# sensorNodev3.net
KiCad netlist of a schematic drawn in EAGLE
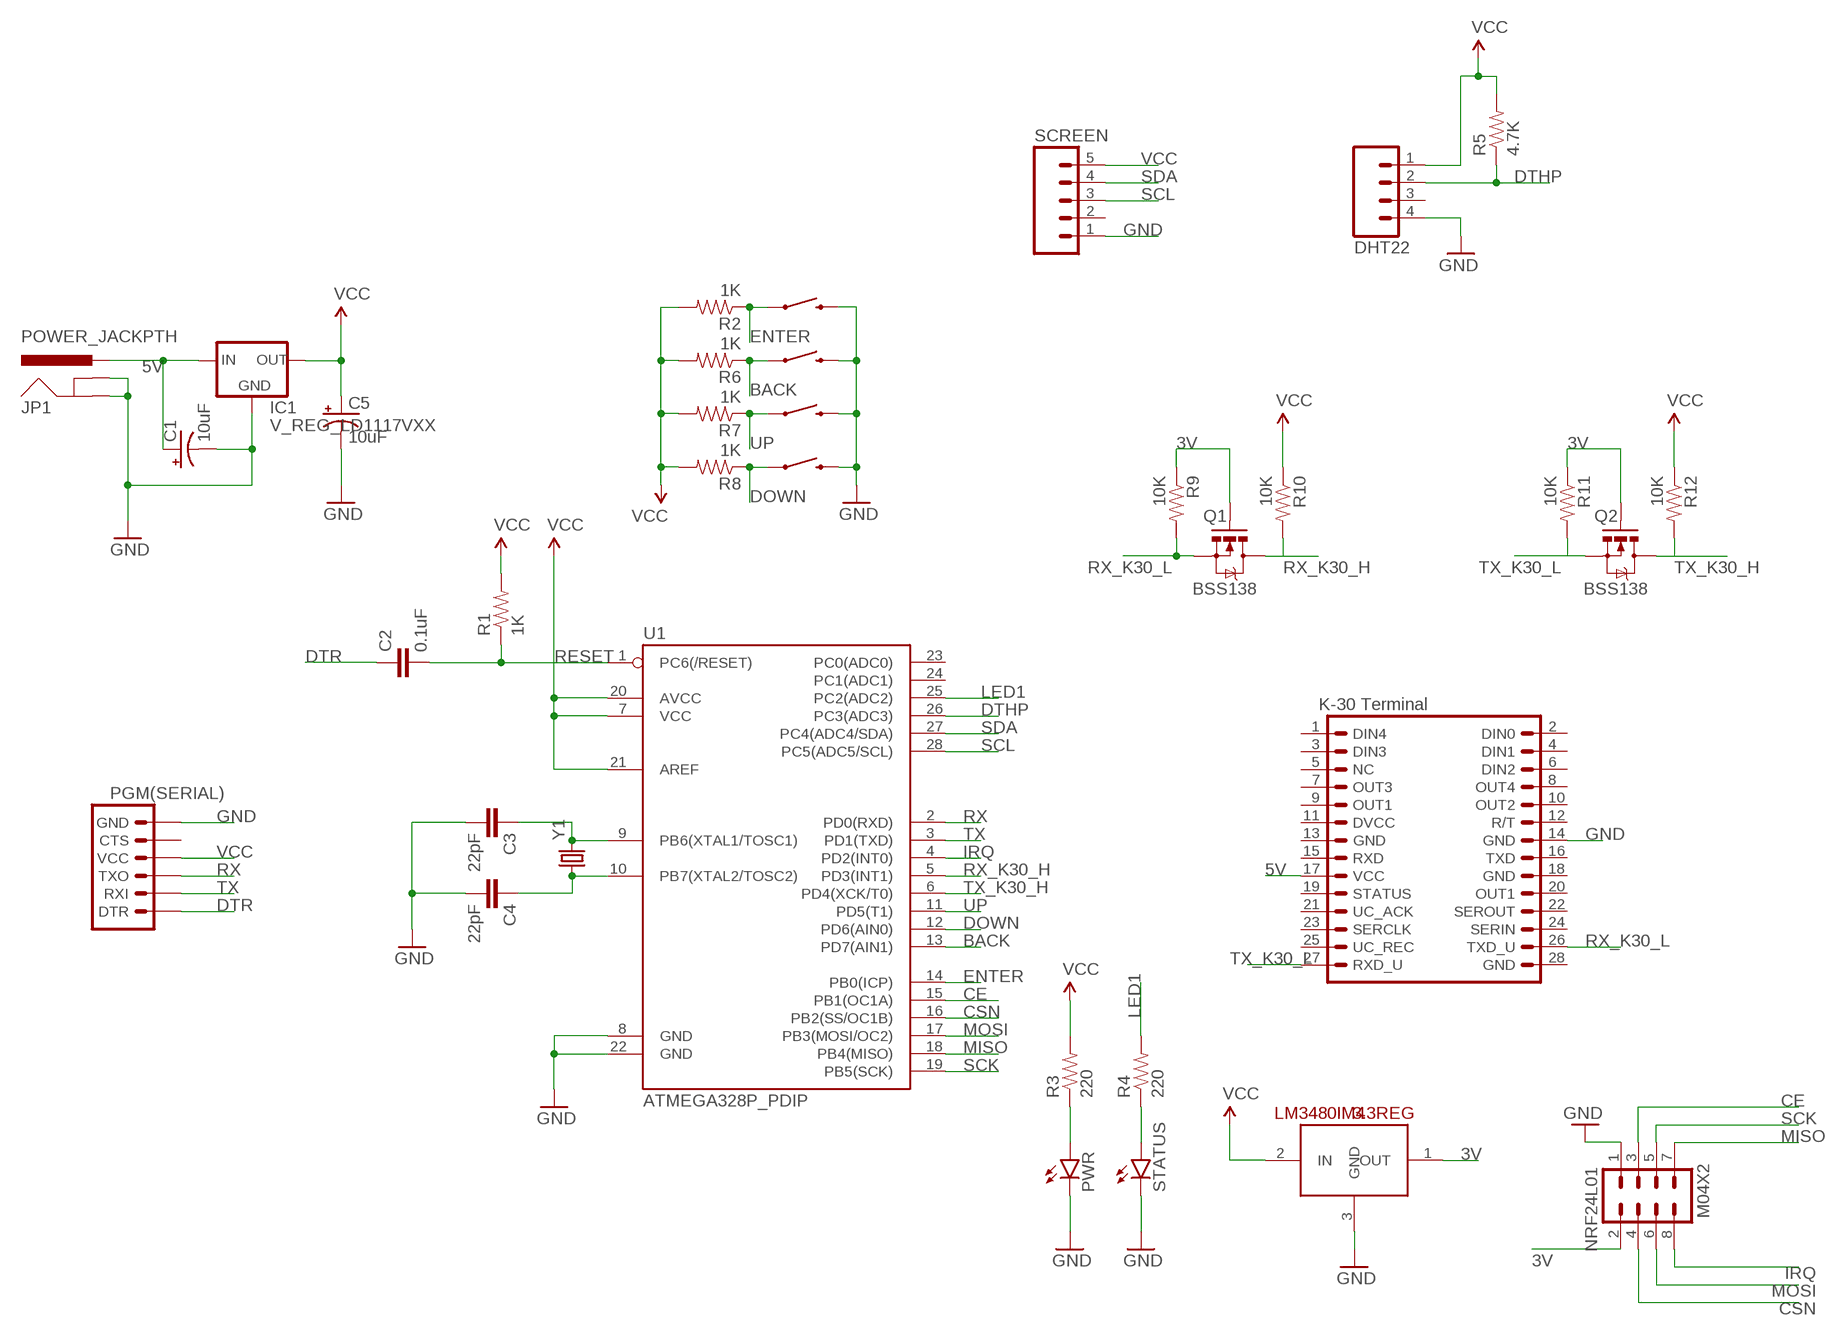
[diagram p0: schematic, sheet 1]

(export (version "E")
  (design (tool "Eeschema 10.0.6"))
  (components
    (comp (ref "3.3REG")
      (value "LM3480IM4")
      (footprint "eagle-import:SOT23-3")
      (libsource (lib "eagle-import") (part "LM3480IM4"))
    )
    (comp (ref "BACK")
      (value "SWITCH-MOMENTARY-2PTH")
      (footprint "eagle-import:TACTILE-PTH")
      (libsource (lib "eagle-import") (part "SWITCH-MOMENTARY-2PTH"))
    )
    (comp (ref "C1")
      (value "10uF")
      (footprint "eagle-import:CPOL-RADIAL-10UF-25V")
      (libsource (lib "eagle-import") (part "CAP_POLPTH2"))
    )
    (comp (ref "C2")
      (value "0.1uF")
      (footprint "eagle-import:0603-CAP")
      (libsource (lib "eagle-import") (part "0.1UF-25V(+80/-20%)(0603)"))
    )
    (comp (ref "C3")
      (value "22pF")
      (footprint "eagle-import:0603-CAP")
      (libsource (lib "eagle-import") (part "22PF-50V-5%(0603)"))
    )
    (comp (ref "C4")
      (value "22pF")
      (footprint "eagle-import:0603-CAP")
      (libsource (lib "eagle-import") (part "22PF-50V-5%(0603)"))
    )
    (comp (ref "C5")
      (value "10uF")
      (footprint "eagle-import:CPOL-RADIAL-10UF-25V")
      (libsource (lib "eagle-import") (part "CAP_POLPTH2"))
    )
    (comp (ref "DHT22")
      (value "M04PTH")
      (footprint "eagle-import:1X04")
      (libsource (lib "eagle-import") (part "M04PTH"))
    )
    (comp (ref "DOWN")
      (value "SWITCH-MOMENTARY-2PTH")
      (footprint "eagle-import:TACTILE-PTH")
      (libsource (lib "eagle-import") (part "SWITCH-MOMENTARY-2PTH"))
    )
    (comp (ref "ENTER")
      (value "SWITCH-MOMENTARY-2PTH")
      (footprint "eagle-import:TACTILE-PTH")
      (libsource (lib "eagle-import") (part "SWITCH-MOMENTARY-2PTH"))
    )
    (comp (ref "IC1")
      (value "V_REG_LD1117VXX")
      (footprint "eagle-import:78XXL")
      (libsource (lib "eagle-import") (part "V_REG_LD1117VXX"))
    )
    (comp (ref "JP1")
      (value "POWER_JACKPTH")
      (footprint "eagle-import:POWER_JACK_PTH")
      (libsource (lib "eagle-import") (part "POWER_JACKPTH"))
    )
    (comp (ref "JP3")
      (value "K-30K-30")
      (footprint "eagle-import:K-30")
      (libsource (lib "eagle-import") (part "K-30K-30"))
    )
    (comp (ref "NRF24L01")
      (value "M04X2")
      (footprint "eagle-import:2X4")
      (libsource (lib "eagle-import") (part "M04X2"))
    )
    (comp (ref "PGM(SERIAL)")
      (value "ARDUINO_SERIAL_PROGRAMPTH")
      (footprint "eagle-import:1X06")
      (libsource (lib "eagle-import") (part "ARDUINO_SERIAL_PROGRAMPTH"))
    )
    (comp (ref "PWR")
      (value "LED0603")
      (footprint "eagle-import:LED-0603")
      (libsource (lib "eagle-import") (part "LED0603"))
    )
    (comp (ref "Q1")
      (value "BSS138")
      (footprint "eagle-import:SOT23-3")
      (libsource (lib "eagle-import") (part "MOSFET-NCHANNELSMD"))
    )
    (comp (ref "Q2")
      (value "BSS138")
      (footprint "eagle-import:SOT23-3")
      (libsource (lib "eagle-import") (part "MOSFET-NCHANNELSMD"))
    )
    (comp (ref "R1")
      (value "1K")
      (footprint "eagle-import:0603-RES")
      (libsource (lib "eagle-import") (part "1KOHM-1/10W-1%(0603)"))
    )
    (comp (ref "R2")
      (value "1K")
      (footprint "eagle-import:0603-RES")
      (libsource (lib "eagle-import") (part "1KOHM-1/10W-1%(0603)"))
    )
    (comp (ref "R3")
      (value "220")
      (footprint "eagle-import:0603-RES")
      (libsource (lib "eagle-import") (part "1KOHM-1/10W-1%(0603)"))
    )
    (comp (ref "R4")
      (value "220")
      (footprint "eagle-import:0603-RES")
      (libsource (lib "eagle-import") (part "1KOHM-1/10W-1%(0603)"))
    )
    (comp (ref "R5")
      (value "4.7K")
      (footprint "eagle-import:0603-RES")
      (libsource (lib "eagle-import") (part "1KOHM-1/10W-1%(0603)"))
    )
    (comp (ref "R6")
      (value "1K")
      (footprint "eagle-import:0603-RES")
      (libsource (lib "eagle-import") (part "1KOHM-1/10W-1%(0603)"))
    )
    (comp (ref "R7")
      (value "1K")
      (footprint "eagle-import:0603-RES")
      (libsource (lib "eagle-import") (part "1KOHM-1/10W-1%(0603)"))
    )
    (comp (ref "R8")
      (value "1K")
      (footprint "eagle-import:0603-RES")
      (libsource (lib "eagle-import") (part "1KOHM-1/10W-1%(0603)"))
    )
    (comp (ref "R9")
      (value "10K")
      (footprint "eagle-import:0603-RES")
      (libsource (lib "eagle-import") (part "RESISTOR0603-RES"))
    )
    (comp (ref "R10")
      (value "10K")
      (footprint "eagle-import:0603-RES")
      (libsource (lib "eagle-import") (part "RESISTOR0603-RES"))
    )
    (comp (ref "R11")
      (value "10K")
      (footprint "eagle-import:0603-RES")
      (libsource (lib "eagle-import") (part "RESISTOR0603-RES"))
    )
    (comp (ref "R12")
      (value "10K")
      (footprint "eagle-import:0603-RES")
      (libsource (lib "eagle-import") (part "RESISTOR0603-RES"))
    )
    (comp (ref "SCREEN")
      (value "M05PTH")
      (footprint "eagle-import:1X05")
      (libsource (lib "eagle-import") (part "M05PTH"))
    )
    (comp (ref "STATUS")
      (value "LED0603")
      (footprint "eagle-import:LED-0603")
      (libsource (lib "eagle-import") (part "LED0603"))
    )
    (comp (ref "U1")
      (value "ATMEGA328P_PDIP")
      (footprint "eagle-import:DIL28-3")
      (libsource (lib "eagle-import") (part "ATMEGA328P_PDIP"))
    )
    (comp (ref "UP")
      (value "SWITCH-MOMENTARY-2PTH")
      (footprint "eagle-import:TACTILE-PTH")
      (libsource (lib "eagle-import") (part "SWITCH-MOMENTARY-2PTH"))
    )
    (comp (ref "Y1")
      (value "CRYSTALHC49US")
      (footprint "eagle-import:HC49US")
      (libsource (lib "eagle-import") (part "CRYSTALHC49US"))
    )
  )
  (nets
    (net (code "1") (name "/3V") (class "Default")
      (node (ref "3.3REG") (pin "1") (pinfunction "OUT_1") (pintype "bidirectional"))
      (node (ref "NRF24L01") (pin "2") (pinfunction "2_2") (pintype "passive"))
      (node (ref "Q1") (pin "1") (pinfunction "G_1") (pintype "passive"))
      (node (ref "Q2") (pin "1") (pinfunction "G_1") (pintype "passive"))
      (node (ref "R11") (pin "1") (pinfunction "1_1") (pintype "passive"))
      (node (ref "R9") (pin "1") (pinfunction "1_1") (pintype "passive"))
    )
    (net (code "2") (name "/5V") (class "Default")
      (node (ref "C1") (pin "1") (pinfunction "+_1") (pintype "passive"))
      (node (ref "IC1") (pin "OUT") (pinfunction "IN_OUT") (pintype "input"))
      (node (ref "JP1") (pin "PWR") (pinfunction "PWR_PWR") (pintype "bidirectional"))
      (node (ref "JP3") (pin "17") (pinfunction "VCC_17") (pintype "bidirectional"))
    )
    (net (code "3") (name "/BACK") (class "Default")
      (node (ref "BACK") (pin "1") (pinfunction "1_1") (pintype "passive"))
      (node (ref "R6") (pin "1") (pinfunction "1_1") (pintype "passive"))
      (node (ref "U1") (pin "13") (pinfunction "PD7(AIN1)_13") (pintype "bidirectional"))
    )
    (net (code "4") (name "/CE") (class "Default")
      (node (ref "NRF24L01") (pin "3") (pinfunction "3_3") (pintype "passive"))
      (node (ref "U1") (pin "15") (pinfunction "PB1(OC1A)_15") (pintype "bidirectional"))
    )
    (net (code "5") (name "/CSN") (class "Default")
      (node (ref "NRF24L01") (pin "4") (pinfunction "4_4") (pintype "passive"))
      (node (ref "U1") (pin "16") (pinfunction "PB2(SS/OC1B)_16") (pintype "bidirectional"))
    )
    (net (code "6") (name "/DOWN") (class "Default")
      (node (ref "DOWN") (pin "1") (pinfunction "1_1") (pintype "passive"))
      (node (ref "R8") (pin "1") (pinfunction "1_1") (pintype "passive"))
      (node (ref "U1") (pin "12") (pinfunction "PD6(AIN0)_12") (pintype "bidirectional"))
    )
    (net (code "7") (name "/DTHP") (class "Default")
      (node (ref "DHT22") (pin "2") (pinfunction "2_2") (pintype "passive"))
      (node (ref "R5") (pin "1") (pinfunction "1_1") (pintype "passive"))
      (node (ref "U1") (pin "26") (pinfunction "PC3(ADC3)_26") (pintype "bidirectional"))
    )
    (net (code "8") (name "/DTR") (class "Default")
      (node (ref "C2") (pin "1") (pinfunction "1_1") (pintype "passive"))
      (node (ref "PGM(SERIAL)") (pin "1") (pinfunction "DTR_1") (pintype "passive"))
    )
    (net (code "9") (name "/ENTER") (class "Default")
      (node (ref "ENTER") (pin "1") (pinfunction "1_1") (pintype "passive"))
      (node (ref "R2") (pin "1") (pinfunction "1_1") (pintype "passive"))
      (node (ref "U1") (pin "14") (pinfunction "PB0(ICP)_14") (pintype "bidirectional"))
    )
    (net (code "10") (name "/IRQ") (class "Default")
      (node (ref "NRF24L01") (pin "8") (pinfunction "8_8") (pintype "passive"))
      (node (ref "U1") (pin "4") (pinfunction "PD2(INT0)_4") (pintype "bidirectional"))
    )
    (net (code "11") (name "/LED1") (class "Default")
      (node (ref "R4") (pin "2") (pinfunction "2_2") (pintype "passive"))
      (node (ref "U1") (pin "25") (pinfunction "PC2(ADC2)_25") (pintype "bidirectional"))
    )
    (net (code "12") (name "/MISO") (class "Default")
      (node (ref "NRF24L01") (pin "7") (pinfunction "7_7") (pintype "passive"))
      (node (ref "U1") (pin "18") (pinfunction "PB4(MISO)_18") (pintype "bidirectional"))
    )
    (net (code "13") (name "/MOSI") (class "Default")
      (node (ref "NRF24L01") (pin "6") (pinfunction "6_6") (pintype "passive"))
      (node (ref "U1") (pin "17") (pinfunction "PB3(MOSI/OC2)_17") (pintype "bidirectional"))
    )
    (net (code "14") (name "/RESET") (class "Default")
      (node (ref "C2") (pin "2") (pinfunction "2_2") (pintype "passive"))
      (node (ref "R1") (pin "1") (pinfunction "1_1") (pintype "passive"))
      (node (ref "U1") (pin "1") (pinfunction "PC6(/RESET)_1") (pintype "bidirectional"))
    )
    (net (code "15") (name "/RX") (class "Default")
      (node (ref "PGM(SERIAL)") (pin "3") (pinfunction "TXO_3") (pintype "passive"))
      (node (ref "U1") (pin "2") (pinfunction "PD0(RXD)_2") (pintype "bidirectional"))
    )
    (net (code "16") (name "/RX_K30_H") (class "Default")
      (node (ref "Q1") (pin "3") (pinfunction "D_3") (pintype "passive"))
      (node (ref "R10") (pin "2") (pinfunction "2_2") (pintype "passive"))
      (node (ref "U1") (pin "5") (pinfunction "PD3(INT1)_5") (pintype "bidirectional"))
    )
    (net (code "17") (name "/RX_K30_L") (class "Default")
      (node (ref "JP3") (pin "26") (pinfunction "TXD_U_26") (pintype "bidirectional"))
      (node (ref "Q1") (pin "2") (pinfunction "S_2") (pintype "passive"))
      (node (ref "R9") (pin "2") (pinfunction "2_2") (pintype "passive"))
    )
    (net (code "18") (name "/SCK") (class "Default")
      (node (ref "NRF24L01") (pin "5") (pinfunction "5_5") (pintype "passive"))
      (node (ref "U1") (pin "19") (pinfunction "PB5(SCK)_19") (pintype "bidirectional"))
    )
    (net (code "19") (name "/SCL") (class "Default")
      (node (ref "SCREEN") (pin "3") (pinfunction "3_3") (pintype "passive"))
      (node (ref "U1") (pin "28") (pinfunction "PC5(ADC5/SCL)_28") (pintype "bidirectional"))
    )
    (net (code "20") (name "/SDA") (class "Default")
      (node (ref "SCREEN") (pin "4") (pinfunction "4_4") (pintype "passive"))
      (node (ref "U1") (pin "27") (pinfunction "PC4(ADC4/SDA)_27") (pintype "bidirectional"))
    )
    (net (code "21") (name "/TX") (class "Default")
      (node (ref "PGM(SERIAL)") (pin "2") (pinfunction "RXI_2") (pintype "passive"))
      (node (ref "U1") (pin "3") (pinfunction "PD1(TXD)_3") (pintype "bidirectional"))
    )
    (net (code "22") (name "/TX_K30_H") (class "Default")
      (node (ref "Q2") (pin "3") (pinfunction "D_3") (pintype "passive"))
      (node (ref "R12") (pin "2") (pinfunction "2_2") (pintype "passive"))
      (node (ref "U1") (pin "6") (pinfunction "PD4(XCK/T0)_6") (pintype "bidirectional"))
    )
    (net (code "23") (name "/TX_K30_L") (class "Default")
      (node (ref "JP3") (pin "27") (pinfunction "RXD_U_27") (pintype "bidirectional"))
      (node (ref "Q2") (pin "2") (pinfunction "S_2") (pintype "passive"))
      (node (ref "R11") (pin "2") (pinfunction "2_2") (pintype "passive"))
    )
    (net (code "24") (name "/UP") (class "Default")
      (node (ref "R7") (pin "1") (pinfunction "1_1") (pintype "passive"))
      (node (ref "U1") (pin "11") (pinfunction "PD5(T1)_11") (pintype "bidirectional"))
      (node (ref "UP") (pin "1") (pinfunction "1_1") (pintype "passive"))
    )
    (net (code "25") (name "GND") (class "Default")
      (node (ref "3.3REG") (pin "3") (pinfunction "GND_3") (pintype "bidirectional"))
      (node (ref "BACK") (pin "3") (pinfunction "2_3") (pintype "passive"))
      (node (ref "C1") (pin "2") (pinfunction "-_2") (pintype "passive"))
      (node (ref "C3") (pin "2") (pinfunction "2_2") (pintype "passive"))
      (node (ref "C4") (pin "2") (pinfunction "2_2") (pintype "passive"))
      (node (ref "C5") (pin "2") (pinfunction "-_2") (pintype "passive"))
      (node (ref "DHT22") (pin "4") (pinfunction "4_4") (pintype "passive"))
      (node (ref "DOWN") (pin "3") (pinfunction "2_3") (pintype "passive"))
      (node (ref "ENTER") (pin "3") (pinfunction "2_3") (pintype "passive"))
      (node (ref "IC1") (pin "IN") (pinfunction "GND_IN") (pintype "input"))
      (node (ref "JP1") (pin "GND") (pinfunction "GND_GND") (pintype "bidirectional"))
      (node (ref "JP1") (pin "GNDBREAK") (pinfunction "GNDBREAK_GNDBREAK") (pintype "bidirectional"))
      (node (ref "JP3") (pin "14") (pinfunction "GND_14") (pintype "bidirectional"))
      (node (ref "NRF24L01") (pin "1") (pinfunction "1_1") (pintype "passive"))
      (node (ref "PGM(SERIAL)") (pin "6") (pinfunction "GND_6") (pintype "passive"))
      (node (ref "PWR") (pin "C") (pinfunction "C_C") (pintype "passive"))
      (node (ref "SCREEN") (pin "1") (pinfunction "1_1") (pintype "passive"))
      (node (ref "STATUS") (pin "C") (pinfunction "C_C") (pintype "passive"))
      (node (ref "U1") (pin "22") (pinfunction "GND_22") (pintype "bidirectional"))
      (node (ref "U1") (pin "8") (pinfunction "GND_8") (pintype "bidirectional"))
      (node (ref "UP") (pin "3") (pinfunction "2_3") (pintype "passive"))
    )
    (net (code "26") (name "Net-(PWR-PadA)") (class "Default")
      (node (ref "PWR") (pin "A") (pinfunction "A_A") (pintype "passive"))
      (node (ref "R3") (pin "1") (pinfunction "1_1") (pintype "passive"))
    )
    (net (code "27") (name "Net-(R4-Pad1)") (class "Default")
      (node (ref "R4") (pin "1") (pinfunction "1_1") (pintype "passive"))
      (node (ref "STATUS") (pin "A") (pinfunction "A_A") (pintype "passive"))
    )
    (net (code "28") (name "Net-(U1-PB6(XTAL1{slash}TOSC1))") (class "Default")
      (node (ref "C3") (pin "1") (pinfunction "1_1") (pintype "passive"))
      (node (ref "U1") (pin "9") (pinfunction "PB6(XTAL1/TOSC1)_9") (pintype "bidirectional"))
      (node (ref "Y1") (pin "2") (pinfunction "2_2") (pintype "passive"))
    )
    (net (code "29") (name "Net-(U1-PB7(XTAL2{slash}TOSC2))") (class "Default")
      (node (ref "C4") (pin "1") (pinfunction "1_1") (pintype "passive"))
      (node (ref "U1") (pin "10") (pinfunction "PB7(XTAL2/TOSC2)_10") (pintype "bidirectional"))
      (node (ref "Y1") (pin "1") (pinfunction "1_1") (pintype "passive"))
    )
    (net (code "30") (name "VCC") (class "Default")
      (node (ref "3.3REG") (pin "2") (pinfunction "IN_2") (pintype "bidirectional"))
      (node (ref "C5") (pin "1") (pinfunction "+_1") (pintype "passive"))
      (node (ref "DHT22") (pin "1") (pinfunction "1_1") (pintype "passive"))
      (node (ref "IC1") (pin "GND") (pinfunction "OUT_GND") (pintype "output"))
      (node (ref "PGM(SERIAL)") (pin "4") (pinfunction "VCC_4") (pintype "passive"))
      (node (ref "R1") (pin "2") (pinfunction "2_2") (pintype "passive"))
      (node (ref "R10") (pin "1") (pinfunction "1_1") (pintype "passive"))
      (node (ref "R12") (pin "1") (pinfunction "1_1") (pintype "passive"))
      (node (ref "R2") (pin "2") (pinfunction "2_2") (pintype "passive"))
      (node (ref "R3") (pin "2") (pinfunction "2_2") (pintype "passive"))
      (node (ref "R5") (pin "2") (pinfunction "2_2") (pintype "passive"))
      (node (ref "R6") (pin "2") (pinfunction "2_2") (pintype "passive"))
      (node (ref "R7") (pin "2") (pinfunction "2_2") (pintype "passive"))
      (node (ref "R8") (pin "2") (pinfunction "2_2") (pintype "passive"))
      (node (ref "SCREEN") (pin "5") (pinfunction "5_5") (pintype "passive"))
      (node (ref "U1") (pin "20") (pinfunction "AVCC_20") (pintype "bidirectional"))
      (node (ref "U1") (pin "21") (pinfunction "AREF_21") (pintype "bidirectional"))
      (node (ref "U1") (pin "7") (pinfunction "VCC_7") (pintype "bidirectional"))
    )
    (net (code "31") (name "unconnected-(DHT22-Pad3)") (class "Default")
      (node (ref "DHT22") (pin "3") (pinfunction "3_3") (pintype "passive"))
    )
    (net (code "32") (name "unconnected-(JP3-DIN0-Pad2)") (class "Default")
      (node (ref "JP3") (pin "2") (pinfunction "DIN0_2") (pintype "bidirectional"))
    )
    (net (code "33") (name "unconnected-(JP3-DIN1-Pad4)") (class "Default")
      (node (ref "JP3") (pin "4") (pinfunction "DIN1_4") (pintype "bidirectional"))
    )
    (net (code "34") (name "unconnected-(JP3-DIN2-Pad6)") (class "Default")
      (node (ref "JP3") (pin "6") (pinfunction "DIN2_6") (pintype "bidirectional"))
    )
    (net (code "35") (name "unconnected-(JP3-DIN3-Pad3)") (class "Default")
      (node (ref "JP3") (pin "3") (pinfunction "DIN3_3") (pintype "bidirectional"))
    )
    (net (code "36") (name "unconnected-(JP3-DIN4-Pad1)") (class "Default")
      (node (ref "JP3") (pin "1") (pinfunction "DIN4_1") (pintype "bidirectional"))
    )
    (net (code "37") (name "unconnected-(JP3-DVCC-Pad11)") (class "Default")
      (node (ref "JP3") (pin "11") (pinfunction "DVCC_11") (pintype "bidirectional"))
    )
    (net (code "38") (name "unconnected-(JP3-GND-Pad13)") (class "Default")
      (node (ref "JP3") (pin "13") (pinfunction "GND_13") (pintype "bidirectional"))
    )
    (net (code "39") (name "unconnected-(JP3-GND-Pad18)") (class "Default")
      (node (ref "JP3") (pin "18") (pinfunction "GND_18") (pintype "bidirectional"))
    )
    (net (code "40") (name "unconnected-(JP3-GND-Pad28)") (class "Default")
      (node (ref "JP3") (pin "28") (pinfunction "GND_28") (pintype "bidirectional"))
    )
    (net (code "41") (name "unconnected-(JP3-NC-Pad5)") (class "Default")
      (node (ref "JP3") (pin "5") (pinfunction "NC_5") (pintype "bidirectional"))
    )
    (net (code "42") (name "unconnected-(JP3-OUT1-Pad9)") (class "Default")
      (node (ref "JP3") (pin "9") (pinfunction "OUT1_9") (pintype "bidirectional"))
    )
    (net (code "43") (name "unconnected-(JP3-OUT1-Pad20)") (class "Default")
      (node (ref "JP3") (pin "20") (pinfunction "OUT1_20") (pintype "bidirectional"))
    )
    (net (code "44") (name "unconnected-(JP3-OUT2-Pad10)") (class "Default")
      (node (ref "JP3") (pin "10") (pinfunction "OUT2_10") (pintype "bidirectional"))
    )
    (net (code "45") (name "unconnected-(JP3-OUT3-Pad7)") (class "Default")
      (node (ref "JP3") (pin "7") (pinfunction "OUT3_7") (pintype "bidirectional"))
    )
    (net (code "46") (name "unconnected-(JP3-OUT4-Pad8)") (class "Default")
      (node (ref "JP3") (pin "8") (pinfunction "OUT4_8") (pintype "bidirectional"))
    )
    (net (code "47") (name "unconnected-(JP3-RXD-Pad15)") (class "Default")
      (node (ref "JP3") (pin "15") (pinfunction "RXD_15") (pintype "bidirectional"))
    )
    (net (code "48") (name "unconnected-(JP3-R{slash}T-Pad12)") (class "Default")
      (node (ref "JP3") (pin "12") (pinfunction "R/T_12") (pintype "bidirectional"))
    )
    (net (code "49") (name "unconnected-(JP3-SERCLK-Pad23)") (class "Default")
      (node (ref "JP3") (pin "23") (pinfunction "SERCLK_23") (pintype "bidirectional"))
    )
    (net (code "50") (name "unconnected-(JP3-SERIN-Pad24)") (class "Default")
      (node (ref "JP3") (pin "24") (pinfunction "SERIN_24") (pintype "bidirectional"))
    )
    (net (code "51") (name "unconnected-(JP3-SEROUT-Pad22)") (class "Default")
      (node (ref "JP3") (pin "22") (pinfunction "SEROUT_22") (pintype "bidirectional"))
    )
    (net (code "52") (name "unconnected-(JP3-STATUS-Pad19)") (class "Default")
      (node (ref "JP3") (pin "19") (pinfunction "STATUS_19") (pintype "bidirectional"))
    )
    (net (code "53") (name "unconnected-(JP3-TXD-Pad16)") (class "Default")
      (node (ref "JP3") (pin "16") (pinfunction "TXD_16") (pintype "bidirectional"))
    )
    (net (code "54") (name "unconnected-(JP3-UC_ACK-Pad21)") (class "Default")
      (node (ref "JP3") (pin "21") (pinfunction "UC_ACK_21") (pintype "bidirectional"))
    )
    (net (code "55") (name "unconnected-(JP3-UC_REC-Pad25)") (class "Default")
      (node (ref "JP3") (pin "25") (pinfunction "UC_REC_25") (pintype "bidirectional"))
    )
    (net (code "56") (name "unconnected-(PGM(SERIAL)-CTS-Pad5)") (class "Default")
      (node (ref "PGM(SERIAL)") (pin "5") (pinfunction "CTS_5") (pintype "passive"))
    )
    (net (code "57") (name "unconnected-(SCREEN-Pad2)") (class "Default")
      (node (ref "SCREEN") (pin "2") (pinfunction "2_2") (pintype "passive"))
    )
    (net (code "58") (name "unconnected-(U1-PC0(ADC0)-Pad23)") (class "Default")
      (node (ref "U1") (pin "23") (pinfunction "PC0(ADC0)_23") (pintype "bidirectional"))
    )
    (net (code "59") (name "unconnected-(U1-PC1(ADC1)-Pad24)") (class "Default")
      (node (ref "U1") (pin "24") (pinfunction "PC1(ADC1)_24") (pintype "bidirectional"))
    )
  )
)
